# SNES_DRONE_LEVEL_SHIFTER_0.net
KiCad netlist of a schematic drawn in Altium Designer
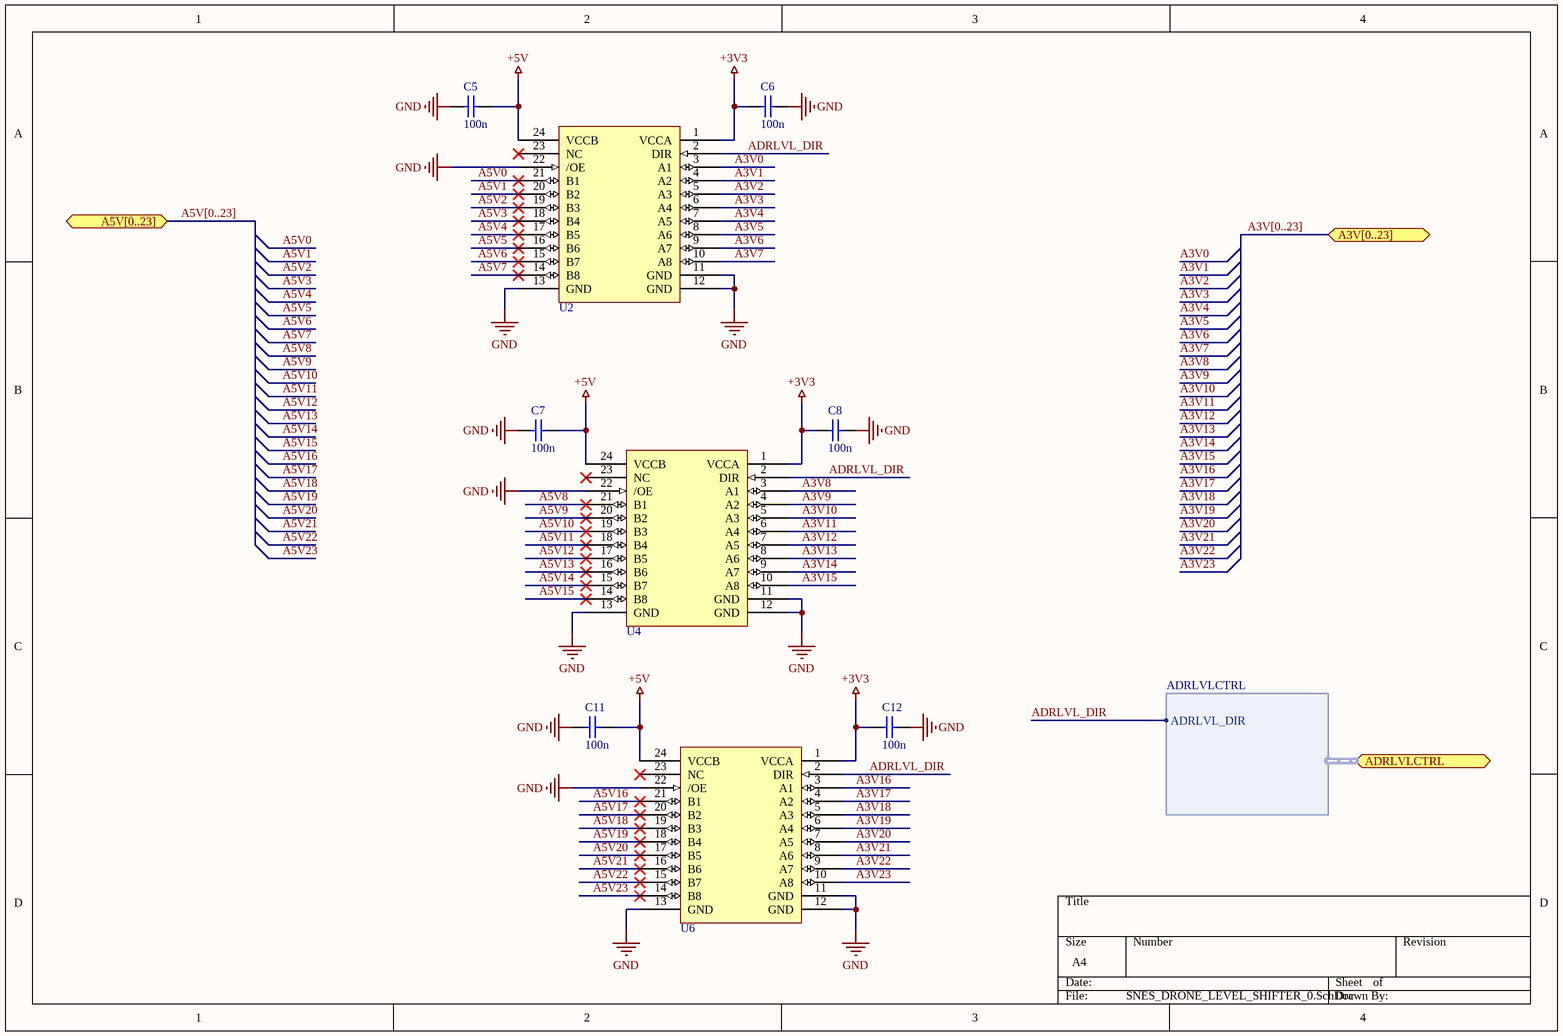
[diagram p0: SNES_DRONE_LEVEL_SHIFTER_0.SchDoc]

(export (version "E")
  (design (tool "Eeschema 10.0.6"))
  (components
    (comp (ref "C5")
      (value "100n")
      (footprint "cap_0603")
      (description "Capacitor")
      (fields (field (name "Comment") "cap_0603"))
      (libsource (lib "mycomponents") (part "cap_0603"))
    )
    (comp (ref "C6")
      (value "100n")
      (footprint "cap_0603")
      (description "Capacitor")
      (fields (field (name "Comment") "cap_0603"))
      (libsource (lib "mycomponents") (part "cap_0603"))
    )
    (comp (ref "C7")
      (value "100n")
      (footprint "cap_0603")
      (description "Capacitor")
      (fields (field (name "Comment") "cap_0603"))
      (libsource (lib "mycomponents") (part "cap_0603"))
    )
    (comp (ref "C8")
      (value "100n")
      (footprint "cap_0603")
      (description "Capacitor")
      (fields (field (name "Comment") "cap_0603"))
      (libsource (lib "mycomponents") (part "cap_0603"))
    )
    (comp (ref "C11")
      (value "100n")
      (footprint "cap_0603")
      (description "Capacitor")
      (fields (field (name "Comment") "cap_0603"))
      (libsource (lib "mycomponents") (part "cap_0603"))
    )
    (comp (ref "C12")
      (value "100n")
      (footprint "cap_0603")
      (description "Capacitor")
      (fields (field (name "Comment") "cap_0603"))
      (libsource (lib "mycomponents") (part "cap_0603"))
    )
    (comp (ref "U2")
      (value "IC_SN74LVCC3245APWR")
      (footprint "TSSOP24")
      (description "Bus-Transceiver, Produktreihe LVC, 8 Eingänge, 50mA, 7ns, 2.3V bis 5.5V, TSSOP 24")
      (libsource (lib "mycomponents") (part "IC_SN74LVCC3245APWR"))
    )
    (comp (ref "U4")
      (value "IC_SN74LVCC3245APWR")
      (footprint "TSSOP24")
      (description "Bus-Transceiver, Produktreihe LVC, 8 Eingänge, 50mA, 7ns, 2.3V bis 5.5V, TSSOP 24")
      (libsource (lib "mycomponents") (part "IC_SN74LVCC3245APWR"))
    )
    (comp (ref "U6")
      (value "IC_SN74LVCC3245APWR")
      (footprint "TSSOP24")
      (description "Bus-Transceiver, Produktreihe LVC, 8 Eingänge, 50mA, 7ns, 2.3V bis 5.5V, TSSOP 24")
      (libsource (lib "mycomponents") (part "IC_SN74LVCC3245APWR"))
    )
  )
  (nets
    (net (code "2") (name "+3V3") (class "Default")
      (node (ref "C12") (pin "2") (pinfunction "2_2") (pintype "passive"))
      (node (ref "C6") (pin "2") (pinfunction "2_2") (pintype "passive"))
      (node (ref "C8") (pin "2") (pinfunction "2_2") (pintype "passive"))
      (node (ref "U2") (pin "1") (pinfunction "VCCA_1") (pintype "power_in"))
      (node (ref "U4") (pin "1") (pinfunction "VCCA_1") (pintype "power_in"))
      (node (ref "U6") (pin "1") (pinfunction "VCCA_1") (pintype "power_in"))
    )
    (net (code "3") (name "+5V") (class "Default")
      (node (ref "C11") (pin "1") (pinfunction "1_1") (pintype "passive"))
      (node (ref "C5") (pin "1") (pinfunction "1_1") (pintype "passive"))
      (node (ref "C7") (pin "1") (pinfunction "1_1") (pintype "passive"))
      (node (ref "U2") (pin "24") (pinfunction "VCCB_24") (pintype "power_in"))
      (node (ref "U4") (pin "24") (pinfunction "VCCB_24") (pintype "power_in"))
      (node (ref "U6") (pin "24") (pinfunction "VCCB_24") (pintype "power_in"))
    )
    (net (code "4") (name "/A3V0") (class "Default")
      (node (ref "U2") (pin "3") (pinfunction "A1_3") (pintype "bidirectional"))
    )
    (net (code "5") (name "/A3V1") (class "Default")
      (node (ref "U2") (pin "4") (pinfunction "A2_4") (pintype "bidirectional"))
    )
    (net (code "6") (name "/A3V2") (class "Default")
      (node (ref "U2") (pin "5") (pinfunction "A3_5") (pintype "bidirectional"))
    )
    (net (code "7") (name "/A3V3") (class "Default")
      (node (ref "U2") (pin "6") (pinfunction "A4_6") (pintype "bidirectional"))
    )
    (net (code "8") (name "/A3V4") (class "Default")
      (node (ref "U2") (pin "7") (pinfunction "A5_7") (pintype "bidirectional"))
    )
    (net (code "9") (name "/A3V5") (class "Default")
      (node (ref "U2") (pin "8") (pinfunction "A6_8") (pintype "bidirectional"))
    )
    (net (code "10") (name "/A3V6") (class "Default")
      (node (ref "U2") (pin "9") (pinfunction "A7_9") (pintype "bidirectional"))
    )
    (net (code "11") (name "/A3V7") (class "Default")
      (node (ref "U2") (pin "10") (pinfunction "A8_10") (pintype "bidirectional"))
    )
    (net (code "12") (name "/A3V8") (class "Default")
      (node (ref "U4") (pin "3") (pinfunction "A1_3") (pintype "bidirectional"))
    )
    (net (code "13") (name "/A3V9") (class "Default")
      (node (ref "U4") (pin "4") (pinfunction "A2_4") (pintype "bidirectional"))
    )
    (net (code "14") (name "/A3V10") (class "Default")
      (node (ref "U4") (pin "5") (pinfunction "A3_5") (pintype "bidirectional"))
    )
    (net (code "15") (name "/A3V11") (class "Default")
      (node (ref "U4") (pin "6") (pinfunction "A4_6") (pintype "bidirectional"))
    )
    (net (code "16") (name "/A3V12") (class "Default")
      (node (ref "U4") (pin "7") (pinfunction "A5_7") (pintype "bidirectional"))
    )
    (net (code "17") (name "/A3V13") (class "Default")
      (node (ref "U4") (pin "8") (pinfunction "A6_8") (pintype "bidirectional"))
    )
    (net (code "18") (name "/A3V14") (class "Default")
      (node (ref "U4") (pin "9") (pinfunction "A7_9") (pintype "bidirectional"))
    )
    (net (code "19") (name "/A3V15") (class "Default")
      (node (ref "U4") (pin "10") (pinfunction "A8_10") (pintype "bidirectional"))
    )
    (net (code "20") (name "/A3V16") (class "Default")
      (node (ref "U6") (pin "3") (pinfunction "A1_3") (pintype "bidirectional"))
    )
    (net (code "21") (name "/A3V17") (class "Default")
      (node (ref "U6") (pin "4") (pinfunction "A2_4") (pintype "bidirectional"))
    )
    (net (code "22") (name "/A3V18") (class "Default")
      (node (ref "U6") (pin "5") (pinfunction "A3_5") (pintype "bidirectional"))
    )
    (net (code "23") (name "/A3V19") (class "Default")
      (node (ref "U6") (pin "6") (pinfunction "A4_6") (pintype "bidirectional"))
    )
    (net (code "24") (name "/A3V20") (class "Default")
      (node (ref "U6") (pin "7") (pinfunction "A5_7") (pintype "bidirectional"))
    )
    (net (code "25") (name "/A3V21") (class "Default")
      (node (ref "U6") (pin "8") (pinfunction "A6_8") (pintype "bidirectional"))
    )
    (net (code "26") (name "/A3V22") (class "Default")
      (node (ref "U6") (pin "9") (pinfunction "A7_9") (pintype "bidirectional"))
    )
    (net (code "27") (name "/A3V23") (class "Default")
      (node (ref "U6") (pin "10") (pinfunction "A8_10") (pintype "bidirectional"))
    )
    (net (code "29") (name "/A5V0") (class "Default")
      (node (ref "U2") (pin "21") (pinfunction "B1_21") (pintype "bidirectional"))
    )
    (net (code "30") (name "/A5V1") (class "Default")
      (node (ref "U2") (pin "20") (pinfunction "B2_20") (pintype "bidirectional"))
    )
    (net (code "31") (name "/A5V2") (class "Default")
      (node (ref "U2") (pin "19") (pinfunction "B3_19") (pintype "bidirectional"))
    )
    (net (code "32") (name "/A5V3") (class "Default")
      (node (ref "U2") (pin "18") (pinfunction "B4_18") (pintype "bidirectional"))
    )
    (net (code "33") (name "/A5V4") (class "Default")
      (node (ref "U2") (pin "17") (pinfunction "B5_17") (pintype "bidirectional+no_connect"))
    )
    (net (code "34") (name "/A5V5") (class "Default")
      (node (ref "U2") (pin "16") (pinfunction "B6_16") (pintype "bidirectional+no_connect"))
    )
    (net (code "35") (name "/A5V6") (class "Default")
      (node (ref "U2") (pin "15") (pinfunction "B7_15") (pintype "bidirectional+no_connect"))
    )
    (net (code "36") (name "/A5V7") (class "Default")
      (node (ref "U2") (pin "14") (pinfunction "B8_14") (pintype "bidirectional+no_connect"))
    )
    (net (code "37") (name "/A5V8") (class "Default")
      (node (ref "U4") (pin "21") (pinfunction "B1_21") (pintype "bidirectional+no_connect"))
    )
    (net (code "38") (name "/A5V9") (class "Default")
      (node (ref "U4") (pin "20") (pinfunction "B2_20") (pintype "bidirectional+no_connect"))
    )
    (net (code "39") (name "/A5V10") (class "Default")
      (node (ref "U4") (pin "19") (pinfunction "B3_19") (pintype "bidirectional+no_connect"))
    )
    (net (code "40") (name "/A5V11") (class "Default")
      (node (ref "U4") (pin "18") (pinfunction "B4_18") (pintype "bidirectional+no_connect"))
    )
    (net (code "41") (name "/A5V12") (class "Default")
      (node (ref "U4") (pin "17") (pinfunction "B5_17") (pintype "bidirectional+no_connect"))
    )
    (net (code "42") (name "/A5V13") (class "Default")
      (node (ref "U4") (pin "16") (pinfunction "B6_16") (pintype "bidirectional+no_connect"))
    )
    (net (code "43") (name "/A5V14") (class "Default")
      (node (ref "U4") (pin "15") (pinfunction "B7_15") (pintype "bidirectional+no_connect"))
    )
    (net (code "44") (name "/A5V15") (class "Default")
      (node (ref "U4") (pin "14") (pinfunction "B8_14") (pintype "bidirectional+no_connect"))
    )
    (net (code "45") (name "/A5V16") (class "Default")
      (node (ref "U6") (pin "21") (pinfunction "B1_21") (pintype "bidirectional"))
    )
    (net (code "46") (name "/A5V17") (class "Default")
      (node (ref "U6") (pin "20") (pinfunction "B2_20") (pintype "bidirectional"))
    )
    (net (code "47") (name "/A5V18") (class "Default")
      (node (ref "U6") (pin "19") (pinfunction "B3_19") (pintype "bidirectional"))
    )
    (net (code "48") (name "/A5V19") (class "Default")
      (node (ref "U6") (pin "18") (pinfunction "B4_18") (pintype "bidirectional"))
    )
    (net (code "49") (name "/A5V20") (class "Default")
      (node (ref "U6") (pin "17") (pinfunction "B5_17") (pintype "bidirectional"))
    )
    (net (code "50") (name "/A5V21") (class "Default")
      (node (ref "U6") (pin "16") (pinfunction "B6_16") (pintype "bidirectional"))
    )
    (net (code "51") (name "/A5V22") (class "Default")
      (node (ref "U6") (pin "15") (pinfunction "B7_15") (pintype "bidirectional"))
    )
    (net (code "52") (name "/A5V23") (class "Default")
      (node (ref "U6") (pin "14") (pinfunction "B8_14") (pintype "bidirectional"))
    )
    (net (code "54") (name "/ADRLVL_DIR") (class "Default")
      (node (ref "U2") (pin "2") (pinfunction "DIR_2") (pintype "input"))
      (node (ref "U4") (pin "2") (pinfunction "DIR_2") (pintype "input"))
      (node (ref "U6") (pin "2") (pinfunction "DIR_2") (pintype "input"))
    )
    (net (code "56") (name "GND") (class "Default")
      (node (ref "C11") (pin "2") (pinfunction "2_2") (pintype "passive"))
      (node (ref "C12") (pin "1") (pinfunction "1_1") (pintype "passive"))
      (node (ref "C5") (pin "2") (pinfunction "2_2") (pintype "passive"))
      (node (ref "C6") (pin "1") (pinfunction "1_1") (pintype "passive"))
      (node (ref "C7") (pin "2") (pinfunction "2_2") (pintype "passive"))
      (node (ref "C8") (pin "1") (pinfunction "1_1") (pintype "passive"))
      (node (ref "U2") (pin "11") (pinfunction "GND_11") (pintype "power_in"))
      (node (ref "U2") (pin "12") (pinfunction "GND_12") (pintype "power_in"))
      (node (ref "U2") (pin "13") (pinfunction "GND_13") (pintype "power_in"))
      (node (ref "U2") (pin "22") (pinfunction "/OE_22") (pintype "input"))
      (node (ref "U4") (pin "11") (pinfunction "GND_11") (pintype "power_in"))
      (node (ref "U4") (pin "12") (pinfunction "GND_12") (pintype "power_in"))
      (node (ref "U4") (pin "13") (pinfunction "GND_13") (pintype "power_in"))
      (node (ref "U4") (pin "22") (pinfunction "/OE_22") (pintype "input"))
      (node (ref "U6") (pin "11") (pinfunction "GND_11") (pintype "power_in"))
      (node (ref "U6") (pin "12") (pinfunction "GND_12") (pintype "power_in"))
      (node (ref "U6") (pin "13") (pinfunction "GND_13") (pintype "power_in"))
      (node (ref "U6") (pin "22") (pinfunction "/OE_22") (pintype "input"))
    )
    (net (code "57") (name "unconnected-(U2-NC-Pad23)") (class "Default")
      (node (ref "U2") (pin "23") (pinfunction "NC_23") (pintype "passive+no_connect"))
    )
    (net (code "58") (name "unconnected-(U4-NC-Pad23)") (class "Default")
      (node (ref "U4") (pin "23") (pinfunction "NC_23") (pintype "passive+no_connect"))
    )
    (net (code "59") (name "unconnected-(U6-NC-Pad23)") (class "Default")
      (node (ref "U6") (pin "23") (pinfunction "NC_23") (pintype "passive+no_connect"))
    )
  )
)
